# 105358-3SC001-01-B_IO_BRD.net
KiCad netlist of a schematic drawn in Altium Designer
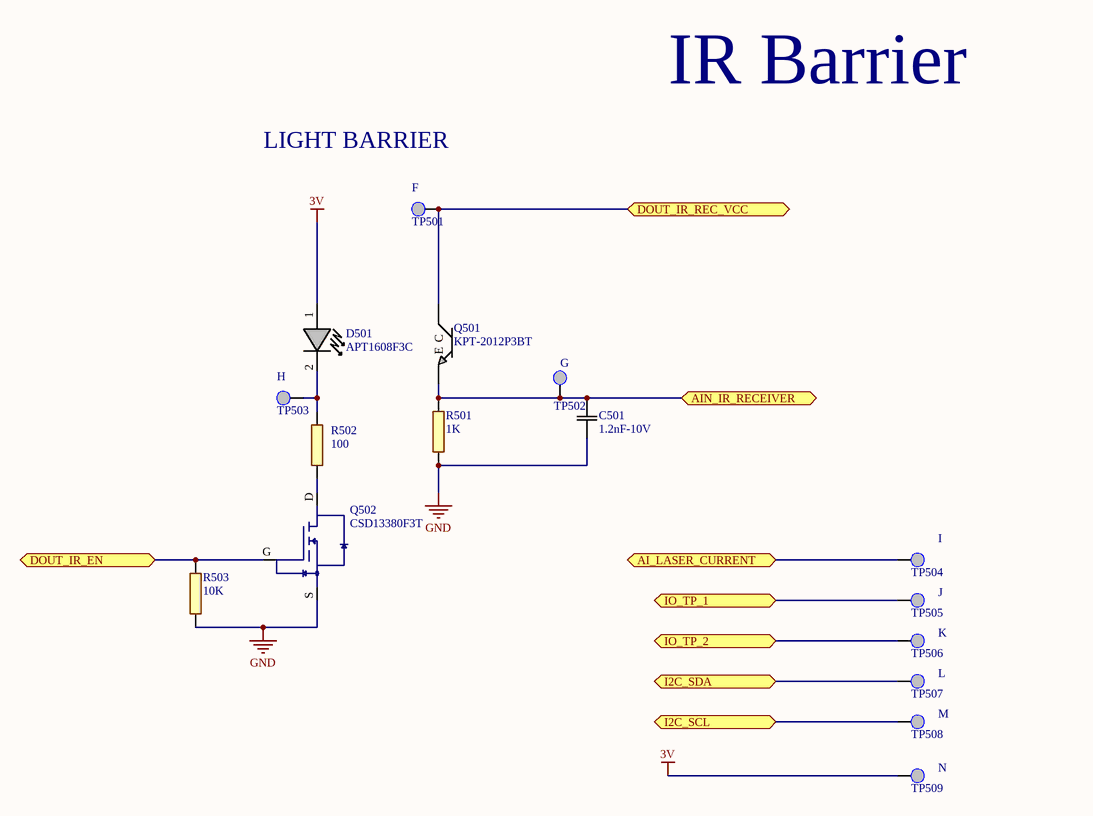
[diagram p0: 105358-3SC001-01-B_IO_BRD.SchDoc]

(export (version "E")
  (design (tool "Eeschema 10.0.6"))
  (components
    (comp (ref "C501")
      (value "1.2nF-10V")
      (footprint "0402C_HIGH_DENSITY")
      (description "1.2nF ±10% 10V U2J Ceramic Capacitor 0402")
      (fields
        (field (name "MANUFACTURER PART NUMBER") "GRM1557U1A122JA01D")
        (field (name "MANUFACTURER") "Murata Electronics North America")
      )
      (libsource (lib "ConnectMedical") (part "0402C-1.2nF-10V"))
    )
    (comp (ref "D501")
      (value "APT1608F3C")
      (footprint "APT1608F3C")
      (description "0603 INFRARED DIODE")
      (fields
        (field (name "MANUFACTURER") "Kingbright")
        (field (name "DIGI-KEY PART NUMBER") "754-1433-1-ND")
      )
      (libsource (lib "ConnectMedical") (part "APT1608F3C"))
    )
    (comp (ref "Q501")
      (value "KPT-2012P3BT")
      (footprint "APT2012P3BT")
      (description "0805 PHOTOTRANSISTOR")
      (fields
        (field (name "MANUFACTURER") "Kingbright")
        (field (name "DIGI-KEY PART NUMBER") "754-1436-1-ND")
      )
      (libsource (lib "ConnectMedical") (part "APT2012P3BT"))
    )
    (comp (ref "Q502")
      (value "CSD13380F3T")
      (footprint "CSD13380F3-DFN40P69X35-3L")
      (description "12V N-CHANNEL FEMTOFET MOSFET")
      (fields (field (name "MANUFACTURER") "Texas Instruments"))
      (libsource (lib "ConnectMedical") (part "CSD13380F3T"))
    )
    (comp (ref "R501")
      (value "1K")
      (footprint "0402R-GENERIC")
      (description "RES SMD 1kOHM 1% 1/16W 0402")
      (fields (field (name "TOLERANCE") "1%") (field (name "POWER") "0.063W"))
      (libsource (lib "ConnectMedical") (part "0402R-1k OHM-1%-0.063W"))
    )
    (comp (ref "R502")
      (value "100")
      (footprint "0402R-GENERIC")
      (description "RES SMD 100OHM 1% 1/16W 0402")
      (fields (field (name "DIGI-KEY PART NUMBER") "311-100LRCT-ND") (field (name "MANUFACTURER") "Yageo"))
      (libsource (lib "ConnectMedical") (part "0402R-100 OHM-1%-0.063W"))
    )
    (comp (ref "R503")
      (value "10K")
      (footprint "0402R-GENERIC")
      (description "RES SMD 10kOHM 1% 1/16W 0402")
      (fields (field (name "DIGI-KEY PART NUMBER") "311-10.0KLRCT-ND") (field (name "MANUFACTURER") "Yageo"))
      (libsource (lib "ConnectMedical") (part "0402R-10k OHM-1%-0.063W"))
    )
    (comp (ref "TP501")
      (value "TEST POINT")
      (footprint "PAD TEST POINT")
      (description "Testing Poiny")
      (libsource (lib "ConnectMedical") (part "TEST POINT"))
    )
    (comp (ref "TP502")
      (value "TEST POINT")
      (footprint "PAD TEST POINT")
      (description "Testing Poiny")
      (libsource (lib "ConnectMedical") (part "TEST POINT"))
    )
    (comp (ref "TP503")
      (value "TEST POINT")
      (footprint "PAD TEST POINT")
      (description "Testing Poiny")
      (libsource (lib "ConnectMedical") (part "TEST POINT"))
    )
    (comp (ref "TP504")
      (value "TEST POINT")
      (footprint "PAD TEST POINT")
      (description "Testing Poiny")
      (libsource (lib "ConnectMedical") (part "TEST POINT"))
    )
    (comp (ref "TP505")
      (value "TEST POINT")
      (footprint "PAD TEST POINT")
      (description "Testing Poiny")
      (libsource (lib "ConnectMedical") (part "TEST POINT"))
    )
    (comp (ref "TP506")
      (value "TEST POINT")
      (footprint "PAD TEST POINT")
      (description "Testing Poiny")
      (libsource (lib "ConnectMedical") (part "TEST POINT"))
    )
    (comp (ref "TP507")
      (value "TEST POINT")
      (footprint "PAD TEST POINT")
      (description "Testing Poiny")
      (libsource (lib "ConnectMedical") (part "TEST POINT"))
    )
    (comp (ref "TP508")
      (value "TEST POINT")
      (footprint "PAD TEST POINT")
      (description "Testing Poiny")
      (libsource (lib "ConnectMedical") (part "TEST POINT"))
    )
    (comp (ref "TP509")
      (value "TEST POINT")
      (footprint "PAD TEST POINT")
      (description "Testing Poiny")
      (libsource (lib "ConnectMedical") (part "TEST POINT"))
    )
  )
  (nets
    (net (code "1") (name "/AIN_IR_RECEIVER") (class "Default")
      (node (ref "C501") (pin "2") (pinfunction "2_2") (pintype "passive"))
      (node (ref "Q501") (pin "1") (pinfunction "E_1") (pintype "passive"))
      (node (ref "R501") (pin "1") (pintype "passive"))
      (node (ref "TP502") (pin "1") (pinfunction "Test_Point_1") (pintype "passive"))
    )
    (net (code "2") (name "/AI_LASER_CURRENT") (class "Default")
      (node (ref "TP504") (pin "1") (pinfunction "Test_Point_1") (pintype "passive"))
    )
    (net (code "3") (name "/DOUT_IR_EN") (class "Default")
      (node (ref "Q502") (pin "G") (pinfunction "1_G") (pintype "passive"))
      (node (ref "R503") (pin "1") (pintype "passive"))
    )
    (net (code "4") (name "/DOUT_IR_REC_VCC") (class "Default")
      (node (ref "Q501") (pin "2") (pinfunction "C_2") (pintype "passive"))
      (node (ref "TP501") (pin "1") (pinfunction "Test_Point_1") (pintype "passive"))
    )
    (net (code "5") (name "/I2C_SCL") (class "Default")
      (node (ref "TP508") (pin "1") (pinfunction "Test_Point_1") (pintype "passive"))
    )
    (net (code "6") (name "/I2C_SDA") (class "Default")
      (node (ref "TP507") (pin "1") (pinfunction "Test_Point_1") (pintype "passive"))
    )
    (net (code "7") (name "/IO_TP_1") (class "Default")
      (node (ref "TP505") (pin "1") (pinfunction "Test_Point_1") (pintype "passive"))
    )
    (net (code "8") (name "/IO_TP_2") (class "Default")
      (node (ref "TP506") (pin "1") (pinfunction "Test_Point_1") (pintype "passive"))
    )
    (net (code "9") (name "3V") (class "Default")
      (node (ref "D501") (pin "1") (pinfunction "A_1") (pintype "passive"))
      (node (ref "TP509") (pin "1") (pinfunction "Test_Point_1") (pintype "passive"))
    )
    (net (code "10") (name "GND") (class "Default")
      (node (ref "C501") (pin "1") (pinfunction "1_1") (pintype "passive"))
      (node (ref "Q502") (pin "S") (pinfunction "2_S") (pintype "passive"))
      (node (ref "R501") (pin "2") (pintype "passive"))
      (node (ref "R503") (pin "2") (pintype "passive"))
    )
    (net (code "11") (name "Net-(D501-K)") (class "Default")
      (node (ref "D501") (pin "2") (pinfunction "K_2") (pintype "passive"))
      (node (ref "R502") (pin "1") (pintype "passive"))
      (node (ref "TP503") (pin "1") (pinfunction "Test_Point_1") (pintype "passive"))
    )
    (net (code "12") (name "Net-(Q502-3)") (class "Default")
      (node (ref "Q502") (pin "D") (pinfunction "3_D") (pintype "passive"))
      (node (ref "R502") (pin "2") (pintype "passive"))
    )
  )
)
